# ShemaMiniM4.net
KiCad netlist of a schematic drawn in Altium Designer
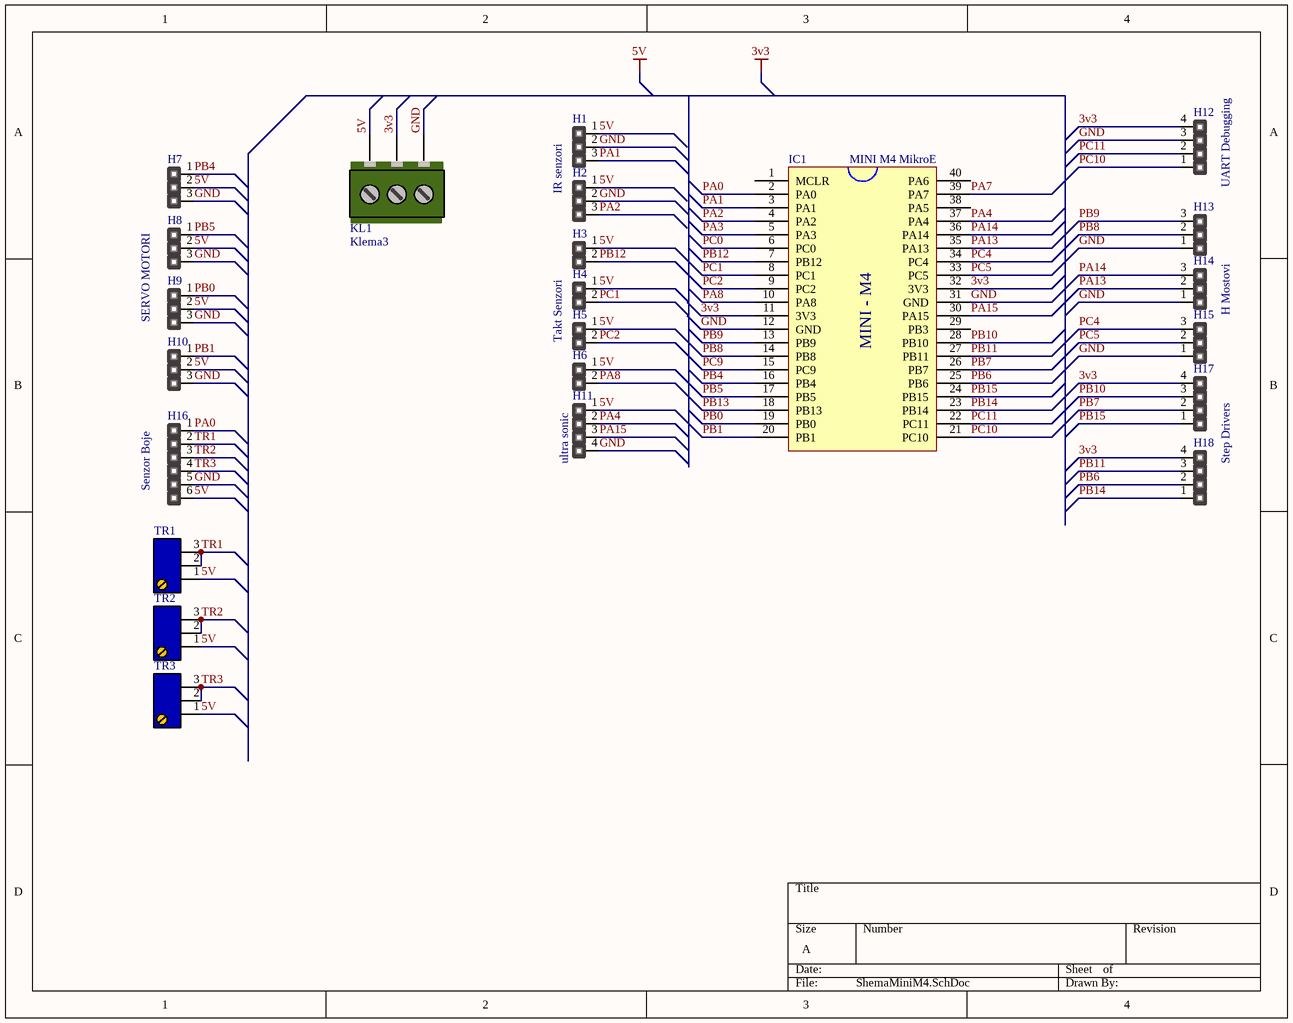
[diagram p0: ShemaMiniM4.SchDoc]

(export (version "E")
  (design (tool "Eeschema 10.0.6"))
  (components
    (comp (ref "H1") (value "Header 1x3") (footprint "Header 1x3") (libsource (lib "") (part "Header 1x3_1")))
    (comp (ref "H2") (value "Header 1x3") (footprint "Header 1x3") (libsource (lib "") (part "Header 1x3_1")))
    (comp (ref "H3")
      (value "Header1x2")
      (footprint "Header1x2")
      (libsource (lib "KILEX LIB SCH") (part "Header1x2"))
    )
    (comp (ref "H4")
      (value "Header1x2")
      (footprint "Header1x2")
      (libsource (lib "KILEX LIB SCH") (part "Header1x2"))
    )
    (comp (ref "H5")
      (value "Header1x2")
      (footprint "Header1x2")
      (libsource (lib "KILEX LIB SCH") (part "Header1x2"))
    )
    (comp (ref "H6")
      (value "Header1x2")
      (footprint "Header1x2")
      (libsource (lib "KILEX LIB SCH") (part "Header1x2"))
    )
    (comp (ref "H7") (value "Header 1x3") (footprint "Header 1x3") (libsource (lib "") (part "Header 1x3_1")))
    (comp (ref "H8") (value "Header 1x3") (footprint "Header 1x3") (libsource (lib "") (part "Header 1x3_1")))
    (comp (ref "H9") (value "Header 1x3") (footprint "Header 1x3") (libsource (lib "") (part "Header 1x3_1")))
    (comp (ref "H10")
      (value "Header 1x3")
      (footprint "Header 1x3")
      (libsource (lib "") (part "Header 1x3_1"))
    )
    (comp (ref "H11") (value "Header1x4") (footprint "Header1x4") (libsource (lib "") (part "Header1x4_1")))
    (comp (ref "H12")
      (value "Header1x4")
      (footprint "Header1x4")
      (libsource (lib "KILEX LIB SCH") (part "Header1x4"))
    )
    (comp (ref "H13")
      (value "Header 1x3")
      (footprint "Header 1x3")
      (libsource (lib "KILEX LIB SCH") (part "Header 1x3"))
    )
    (comp (ref "H14")
      (value "Header 1x3")
      (footprint "Header 1x3")
      (libsource (lib "KILEX LIB SCH") (part "Header 1x3"))
    )
    (comp (ref "H15")
      (value "Header 1x3")
      (footprint "Header 1x3")
      (libsource (lib "KILEX LIB SCH") (part "Header 1x3"))
    )
    (comp (ref "H16")
      (value "Header1x6")
      (footprint "Header1x6")
      (libsource (lib "KILEX LIB SCH") (part "Header1x6"))
    )
    (comp (ref "H17")
      (value "Header1x4")
      (footprint "Header1x4")
      (libsource (lib "KILEX LIB SCH") (part "Header1x4"))
    )
    (comp (ref "H18")
      (value "Header1x4")
      (footprint "Header1x4")
      (libsource (lib "KILEX LIB SCH") (part "Header1x4"))
    )
    (comp (ref "IC1")
      (value "MINI M4 MikroE")
      (footprint "DIP40")
      (libsource (lib "KILEX LIB SCH") (part "MINI M4 MikroE"))
    )
    (comp (ref "KL1") (value "Klema3") (footprint "Klema3") (libsource (lib "KILEX LIB SCH") (part "Klema3")))
    (comp (ref "TR1") (value "TRIM") (footprint "TRIM") (libsource (lib "KILEX LIB SCH") (part "TRIM")))
    (comp (ref "TR2") (value "TRIM") (footprint "TRIM") (libsource (lib "KILEX LIB SCH") (part "TRIM")))
    (comp (ref "TR3") (value "TRIM") (footprint "TRIM") (libsource (lib "KILEX LIB SCH") (part "TRIM")))
  )
  (nets
    (net (code "1") (name "/GND") (class "Default")
      (node (ref "H1") (pin "2") (pinfunction "2_2") (pintype "passive"))
      (node (ref "H10") (pin "3") (pinfunction "3_3") (pintype "passive"))
      (node (ref "H11") (pin "4") (pinfunction "4_4") (pintype "passive"))
      (node (ref "H12") (pin "3") (pinfunction "3_3") (pintype "passive"))
      (node (ref "H13") (pin "1") (pinfunction "1_1") (pintype "passive"))
      (node (ref "H14") (pin "1") (pinfunction "1_1") (pintype "passive"))
      (node (ref "H15") (pin "1") (pinfunction "1_1") (pintype "passive"))
      (node (ref "H16") (pin "5") (pinfunction "5_5") (pintype "passive"))
      (node (ref "H2") (pin "2") (pinfunction "2_2") (pintype "passive"))
      (node (ref "H7") (pin "3") (pinfunction "3_3") (pintype "passive"))
      (node (ref "H8") (pin "3") (pinfunction "3_3") (pintype "passive"))
      (node (ref "H9") (pin "3") (pinfunction "3_3") (pintype "passive"))
      (node (ref "IC1") (pin "12") (pinfunction "GND_12") (pintype "passive"))
      (node (ref "IC1") (pin "31") (pinfunction "GND_31") (pintype "passive"))
      (node (ref "KL1") (pin "1") (pinfunction "1_1") (pintype "passive"))
    )
    (net (code "2") (name "/PA0") (class "Default")
      (node (ref "H16") (pin "1") (pinfunction "1_1") (pintype "passive"))
      (node (ref "IC1") (pin "2") (pinfunction "PA0_2") (pintype "passive"))
    )
    (net (code "3") (name "/PA1") (class "Default")
      (node (ref "H1") (pin "3") (pinfunction "3_3") (pintype "passive"))
      (node (ref "IC1") (pin "3") (pinfunction "PA1_3") (pintype "passive"))
    )
    (net (code "4") (name "/PA2") (class "Default")
      (node (ref "H2") (pin "3") (pinfunction "3_3") (pintype "passive"))
      (node (ref "IC1") (pin "4") (pinfunction "PA2_4") (pintype "passive"))
    )
    (net (code "5") (name "/PA3") (class "Default")
      (node (ref "IC1") (pin "5") (pinfunction "PA3_5") (pintype "passive"))
    )
    (net (code "6") (name "/PA4") (class "Default")
      (node (ref "H11") (pin "2") (pinfunction "2_2") (pintype "passive"))
      (node (ref "IC1") (pin "37") (pinfunction "PA4_37") (pintype "passive"))
    )
    (net (code "7") (name "/PA7") (class "Default")
      (node (ref "IC1") (pin "39") (pinfunction "PA7_39") (pintype "passive"))
    )
    (net (code "8") (name "/PA8") (class "Default")
      (node (ref "H6") (pin "2") (pinfunction "2_2") (pintype "passive"))
      (node (ref "IC1") (pin "10") (pinfunction "PA8_10") (pintype "passive"))
    )
    (net (code "9") (name "/PA13") (class "Default")
      (node (ref "H14") (pin "2") (pinfunction "2_2") (pintype "passive"))
      (node (ref "IC1") (pin "35") (pinfunction "PA13_35") (pintype "passive"))
    )
    (net (code "10") (name "/PA14") (class "Default")
      (node (ref "H14") (pin "3") (pinfunction "3_3") (pintype "passive"))
      (node (ref "IC1") (pin "36") (pinfunction "PA14_36") (pintype "passive"))
    )
    (net (code "11") (name "/PA15") (class "Default")
      (node (ref "H11") (pin "3") (pinfunction "3_3") (pintype "passive"))
      (node (ref "IC1") (pin "30") (pinfunction "PA15_30") (pintype "passive"))
    )
    (net (code "12") (name "/PB0") (class "Default")
      (node (ref "H9") (pin "1") (pinfunction "1_1") (pintype "passive"))
      (node (ref "IC1") (pin "19") (pinfunction "PB0_19") (pintype "passive"))
    )
    (net (code "13") (name "/PB1") (class "Default")
      (node (ref "H10") (pin "1") (pinfunction "1_1") (pintype "passive"))
      (node (ref "IC1") (pin "20") (pinfunction "PB1_20") (pintype "passive"))
    )
    (net (code "14") (name "/PB4") (class "Default")
      (node (ref "H7") (pin "1") (pinfunction "1_1") (pintype "passive"))
      (node (ref "IC1") (pin "16") (pinfunction "PB4_16") (pintype "passive"))
    )
    (net (code "15") (name "/PB5") (class "Default")
      (node (ref "H8") (pin "1") (pinfunction "1_1") (pintype "passive"))
      (node (ref "IC1") (pin "17") (pinfunction "PB5_17") (pintype "passive"))
    )
    (net (code "16") (name "/PB6") (class "Default")
      (node (ref "H18") (pin "2") (pinfunction "2_2") (pintype "passive"))
      (node (ref "IC1") (pin "25") (pinfunction "PB6_25") (pintype "passive"))
    )
    (net (code "17") (name "/PB7") (class "Default")
      (node (ref "H17") (pin "2") (pinfunction "2_2") (pintype "passive"))
      (node (ref "IC1") (pin "26") (pinfunction "PB7_26") (pintype "passive"))
    )
    (net (code "18") (name "/PB8") (class "Default")
      (node (ref "H13") (pin "2") (pinfunction "2_2") (pintype "passive"))
      (node (ref "IC1") (pin "14") (pinfunction "PB8_14") (pintype "passive"))
    )
    (net (code "19") (name "/PB9") (class "Default")
      (node (ref "H13") (pin "3") (pinfunction "3_3") (pintype "passive"))
      (node (ref "IC1") (pin "13") (pinfunction "PB9_13") (pintype "passive"))
    )
    (net (code "20") (name "/PB10") (class "Default")
      (node (ref "H17") (pin "3") (pinfunction "3_3") (pintype "passive"))
      (node (ref "IC1") (pin "28") (pinfunction "PB10_28") (pintype "passive"))
    )
    (net (code "21") (name "/PB11") (class "Default")
      (node (ref "H18") (pin "3") (pinfunction "3_3") (pintype "passive"))
      (node (ref "IC1") (pin "27") (pinfunction "PB11_27") (pintype "passive"))
    )
    (net (code "22") (name "/PB12") (class "Default")
      (node (ref "H3") (pin "2") (pinfunction "2_2") (pintype "passive"))
      (node (ref "IC1") (pin "7") (pinfunction "PB12_7") (pintype "passive"))
    )
    (net (code "23") (name "/PB13") (class "Default")
      (node (ref "IC1") (pin "18") (pinfunction "PB13_18") (pintype "passive"))
    )
    (net (code "24") (name "/PB14") (class "Default")
      (node (ref "H18") (pin "1") (pinfunction "1_1") (pintype "passive"))
      (node (ref "IC1") (pin "23") (pinfunction "PB14_23") (pintype "passive"))
    )
    (net (code "25") (name "/PB15") (class "Default")
      (node (ref "H17") (pin "1") (pinfunction "1_1") (pintype "passive"))
      (node (ref "IC1") (pin "24") (pinfunction "PB15_24") (pintype "passive"))
    )
    (net (code "26") (name "/PC0") (class "Default")
      (node (ref "IC1") (pin "6") (pinfunction "PC0_6") (pintype "passive"))
    )
    (net (code "27") (name "/PC1") (class "Default")
      (node (ref "H4") (pin "2") (pinfunction "2_2") (pintype "passive"))
      (node (ref "IC1") (pin "8") (pinfunction "PC1_8") (pintype "passive"))
    )
    (net (code "28") (name "/PC2") (class "Default")
      (node (ref "H5") (pin "2") (pinfunction "2_2") (pintype "passive"))
      (node (ref "IC1") (pin "9") (pinfunction "PC2_9") (pintype "passive"))
    )
    (net (code "29") (name "/PC4") (class "Default")
      (node (ref "H15") (pin "3") (pinfunction "3_3") (pintype "passive"))
      (node (ref "IC1") (pin "34") (pinfunction "PC4_34") (pintype "passive"))
    )
    (net (code "30") (name "/PC5") (class "Default")
      (node (ref "H15") (pin "2") (pinfunction "2_2") (pintype "passive"))
      (node (ref "IC1") (pin "33") (pinfunction "PC5_33") (pintype "passive"))
    )
    (net (code "31") (name "/PC9") (class "Default")
      (node (ref "IC1") (pin "15") (pinfunction "PC9_15") (pintype "passive"))
    )
    (net (code "32") (name "/PC10") (class "Default")
      (node (ref "H12") (pin "1") (pinfunction "1_1") (pintype "passive"))
      (node (ref "IC1") (pin "21") (pinfunction "PC10_21") (pintype "passive"))
    )
    (net (code "33") (name "/PC11") (class "Default")
      (node (ref "H12") (pin "2") (pinfunction "2_2") (pintype "passive"))
      (node (ref "IC1") (pin "22") (pinfunction "PC11_22") (pintype "passive"))
    )
    (net (code "34") (name "/TR1") (class "Default")
      (node (ref "H16") (pin "2") (pinfunction "2_2") (pintype "passive"))
      (node (ref "TR1") (pin "2") (pinfunction "2_2") (pintype "passive"))
      (node (ref "TR1") (pin "3") (pinfunction "3_3") (pintype "passive"))
    )
    (net (code "35") (name "/TR2") (class "Default")
      (node (ref "H16") (pin "3") (pinfunction "3_3") (pintype "passive"))
      (node (ref "TR2") (pin "2") (pinfunction "2_2") (pintype "passive"))
      (node (ref "TR2") (pin "3") (pinfunction "3_3") (pintype "passive"))
    )
    (net (code "36") (name "/TR3") (class "Default")
      (node (ref "H16") (pin "4") (pinfunction "4_4") (pintype "passive"))
      (node (ref "TR3") (pin "2") (pinfunction "2_2") (pintype "passive"))
      (node (ref "TR3") (pin "3") (pinfunction "3_3") (pintype "passive"))
    )
    (net (code "37") (name "3v3") (class "Default")
      (node (ref "H12") (pin "4") (pinfunction "4_4") (pintype "passive"))
      (node (ref "H17") (pin "4") (pinfunction "4_4") (pintype "passive"))
      (node (ref "H18") (pin "4") (pinfunction "4_4") (pintype "passive"))
      (node (ref "IC1") (pin "11") (pinfunction "3V3_11") (pintype "passive"))
      (node (ref "IC1") (pin "32") (pinfunction "3V3_32") (pintype "passive"))
      (node (ref "KL1") (pin "2") (pinfunction "2_2") (pintype "passive"))
    )
    (net (code "38") (name "5V") (class "Default")
      (node (ref "H1") (pin "1") (pinfunction "1_1") (pintype "passive"))
      (node (ref "H10") (pin "2") (pinfunction "2_2") (pintype "passive"))
      (node (ref "H11") (pin "1") (pinfunction "1_1") (pintype "passive"))
      (node (ref "H16") (pin "6") (pinfunction "6_6") (pintype "passive"))
      (node (ref "H2") (pin "1") (pinfunction "1_1") (pintype "passive"))
      (node (ref "H3") (pin "1") (pinfunction "1_1") (pintype "passive"))
      (node (ref "H4") (pin "1") (pinfunction "1_1") (pintype "passive"))
      (node (ref "H5") (pin "1") (pinfunction "1_1") (pintype "passive"))
      (node (ref "H6") (pin "1") (pinfunction "1_1") (pintype "passive"))
      (node (ref "H7") (pin "2") (pinfunction "2_2") (pintype "passive"))
      (node (ref "H8") (pin "2") (pinfunction "2_2") (pintype "passive"))
      (node (ref "H9") (pin "2") (pinfunction "2_2") (pintype "passive"))
      (node (ref "KL1") (pin "3") (pinfunction "3_3") (pintype "passive"))
      (node (ref "TR1") (pin "1") (pinfunction "1_1") (pintype "passive"))
      (node (ref "TR2") (pin "1") (pinfunction "1_1") (pintype "passive"))
      (node (ref "TR3") (pin "1") (pinfunction "1_1") (pintype "passive"))
    )
    (net (code "39") (name "unconnected-(IC1-MCLR-Pad1)") (class "Default")
      (node (ref "IC1") (pin "1") (pinfunction "MCLR_1") (pintype "passive"))
    )
    (net (code "40") (name "unconnected-(IC1-PA5-Pad38)") (class "Default")
      (node (ref "IC1") (pin "38") (pinfunction "PA5_38") (pintype "passive"))
    )
    (net (code "41") (name "unconnected-(IC1-PA6-Pad40)") (class "Default")
      (node (ref "IC1") (pin "40") (pinfunction "PA6_40") (pintype "passive"))
    )
    (net (code "42") (name "unconnected-(IC1-PB3-Pad29)") (class "Default")
      (node (ref "IC1") (pin "29") (pinfunction "PB3_29") (pintype "passive"))
    )
  )
)
